# H01R0_Frontend_1.net
KiCad netlist of a schematic drawn in Altium Designer
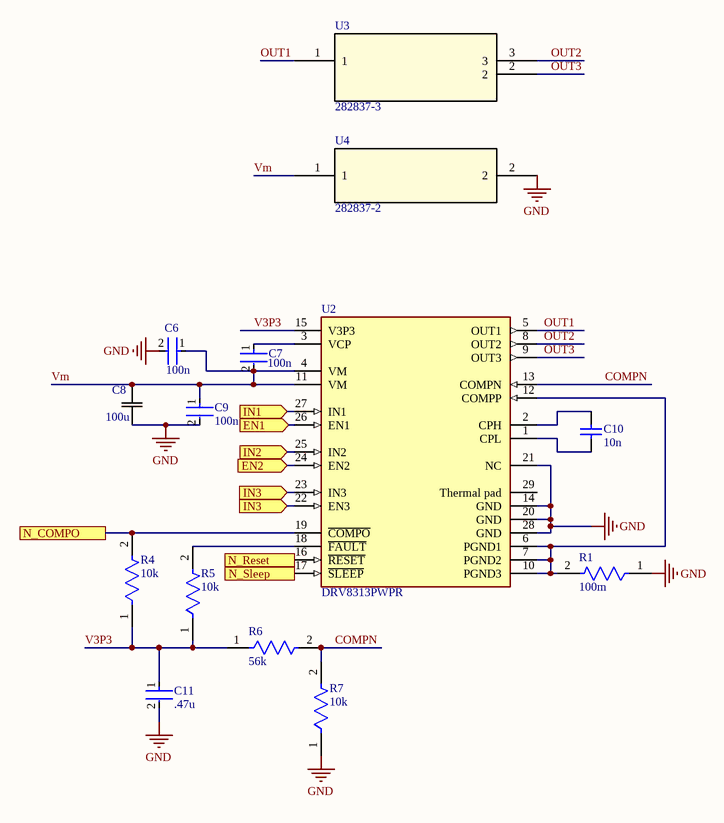
[diagram p0: H01R0_Frontend 1.SchDoc]

(export (version "E")
  (design (tool "Eeschema 10.0.6"))
  (components
    (comp (ref "C6")
      (value "100n")
      (footprint "FP-1812-L_4_5_0_3-W_3_2_0-IPC_C")
      (description "General Purpose Ceramic Capacitor, 1812, 100nF, 10%, X7R, 15%, 100V")
      (fields (field (name "TOLERANCE") "10%") (field (name "VOLTAGE") "100V"))
      (libsource (lib "Altium Content Vault") (part "02cd4be3c70576c341d710602a673aa"))
    )
    (comp (ref "C7")
      (value "100n")
      (footprint "FP-1812-L_4_5_0_3-W_3_2_0-IPC_C")
      (description "General Purpose Ceramic Capacitor, 1812, 100nF, 10%, X7R, 15%, 100V")
      (fields (field (name "TOLERANCE") "10%") (field (name "VOLTAGE") "100V"))
      (libsource (lib "Altium Content Vault") (part "02cd4be3c70576c341d710602a673aa"))
    )
    (comp (ref "C8")
      (value "100u")
      (footprint "CAP_CL31A_SAM")
      (description "No Description Available")
      (fields
        (field (name "MANUFACTURER_PART_NUMBER") "CL31A107MQHNNWE")
        (field (name "COPYRIGHT") "Copyright (C) 2025 Ultra Librarian. All rights reserved.")
      )
      (libsource (lib "Phone Jig") (part "CL31A107MQHNNWE"))
    )
    (comp (ref "C9")
      (value "100n")
      (footprint "FP-1812-L_4_5_0_3-W_3_2_0-IPC_C")
      (description "General Purpose Ceramic Capacitor, 1812, 100nF, 10%, X7R, 15%, 100V")
      (fields (field (name "TOLERANCE") "10%") (field (name "VOLTAGE") "100V"))
      (libsource (lib "Altium Content Vault") (part "02cd4be3c70576c341d710602a673aa"))
    )
    (comp (ref "C10")
      (value "10n")
      (footprint "CAPC1608X92X38NL15T08")
      (fields (field (name "PART NUMBER") "VJ0603Y103KXBAC") (field (name "MANUFACTURER") "Vitramon"))
      (libsource (lib "Altium Content Vault") (part "CAP"))
    )
    (comp (ref "C11")
      (value ".47u")
      (footprint "FP-C1206C-EB-MFG")
      (description "C1206 0.47 μF X7R 10.00% 25 V")
      (fields
        (field (name "OCTOPART") "https://octopart.com/c1206c474k3rac7210-kemet-13188669")
        (field (name "MANUFACTURER") "KEMET")
      )
      (libsource (lib "Altium Content Vault") (part "b4654b650e69147ec39a6b967a45e02"))
    )
    (comp (ref "R1")
      (value "100m")
      (footprint "FP-PCS2512-IPC_C")
      (description "2W 0.100 OHMS 0.5% 2512")
      (libsource (lib "Altium Content Vault") (part "1029c3af85768c4190bb7ad29bc67b5"))
    )
    (comp (ref "R4")
      (value "10k")
      (footprint "FP-CRCW2010-e3-IPC_B")
      (description "RES Thick Film, 10kΩ, 1%, 0.75W, 100ppm/°C, 2010")
      (fields (field (name "TOLERANCE") "1%"))
      (libsource (lib "Altium Content Vault") (part "1029c3af85768c4190bb7ad29bc67b5"))
    )
    (comp (ref "R5")
      (value "10k")
      (footprint "FP-CRCW2010-e3-IPC_B")
      (description "RES Thick Film, 10kΩ, 1%, 0.75W, 100ppm/°C, 2010")
      (fields (field (name "TOLERANCE") "1%"))
      (libsource (lib "Altium Content Vault") (part "1029c3af85768c4190bb7ad29bc67b5"))
    )
    (comp (ref "R6")
      (value "56k")
      (footprint "FP-SMA-A0207-MFG")
      (description "SMA-A 0207 56KΩ 1W 15ppm/ºC 0.10% 350V")
      (fields (field (name "MANUFACTURER") "TE Connectivity") (field (name "TOLERANCE") "0.001"))
      (libsource (lib "Altium Content Vault") (part "1029c3af85768c4190bb7ad29bc67b5"))
    )
    (comp (ref "R7")
      (value "10k")
      (footprint "FP-CRCW2010-e3-IPC_B")
      (description "RES Thick Film, 10kΩ, 1%, 0.75W, 100ppm/°C, 2010")
      (fields (field (name "TOLERANCE") "1%"))
      (libsource (lib "Altium Content Vault") (part "1029c3af85768c4190bb7ad29bc67b5"))
    )
    (comp (ref "U2")
      (value "DRV8313PWPR")
      (footprint "FP-PWP0028C-IPC_B")
      (description "IC MOTOR DRIVER 8V-60V 28HTSSOP")
      (libsource (lib "Altium Content Vault") (part "6c5e8d1d79df7918d4eb9ae5de6b4b8"))
    )
    (comp (ref "U3")
      (value "282837-3")
      (footprint "282837-3_TYC")
      (description "TERMI-BLOK PCB MOUNT 3P")
      (fields (field (name "COPYRIGHT") "Copyright (C) 2025 Ultra Librarian. All rights reserved."))
      (libsource (lib "Phone Jig") (part "282837-3"))
    )
    (comp (ref "U4")
      (value "282837-2")
      (footprint "282837-2_TYC")
      (description "TERMI-BLOK PCB MOUNT 2P")
      (fields (field (name "COPYRIGHT") "Copyright (C) 2025 Ultra Librarian. All rights reserved."))
      (libsource (lib "Phone Jig") (part "282837-2"))
    )
  )
  (nets
    (net (code "1") (name "/COMPN") (class "Default")
      (node (ref "R6") (pin "2") (pinfunction "2_2") (pintype "passive"))
      (node (ref "R7") (pin "2") (pinfunction "2_2") (pintype "passive"))
      (node (ref "U2") (pin "13") (pinfunction "COMPN_13") (pintype "input"))
    )
    (net (code "2") (name "/EN1") (class "Default")
      (node (ref "U2") (pin "26") (pinfunction "EN1_26") (pintype "input"))
    )
    (net (code "3") (name "/EN2") (class "Default")
      (node (ref "U2") (pin "24") (pinfunction "EN2_24") (pintype "input"))
    )
    (net (code "4") (name "/IN1") (class "Default")
      (node (ref "U2") (pin "27") (pinfunction "IN1_27") (pintype "input"))
    )
    (net (code "5") (name "/IN2") (class "Default")
      (node (ref "U2") (pin "25") (pinfunction "IN2_25") (pintype "input"))
    )
    (net (code "6") (name "/IN3") (class "Default")
      (node (ref "U2") (pin "22") (pinfunction "EN3_22") (pintype "input"))
      (node (ref "U2") (pin "23") (pinfunction "IN3_23") (pintype "input"))
    )
    (net (code "7") (name "/N_COMPO") (class "Default")
      (node (ref "R4") (pin "2") (pinfunction "2_2") (pintype "passive"))
      (node (ref "U2") (pin "19") (pinfunction "~{COMPO}_19") (pintype "open_collector"))
    )
    (net (code "8") (name "/N_Reset") (class "Default")
      (node (ref "U2") (pin "16") (pinfunction "~{RESET}_16") (pintype "input"))
    )
    (net (code "9") (name "/N_Sleep") (class "Default")
      (node (ref "U2") (pin "17") (pinfunction "~{SLEEP}_17") (pintype "input"))
    )
    (net (code "10") (name "/OUT1") (class "Default")
      (node (ref "U2") (pin "5") (pinfunction "OUT1_5") (pintype "output"))
      (node (ref "U3") (pin "1") (pinfunction "1_1") (pintype "passive"))
    )
    (net (code "11") (name "/OUT2") (class "Default")
      (node (ref "U2") (pin "8") (pinfunction "OUT2_8") (pintype "output"))
      (node (ref "U3") (pin "3") (pinfunction "3_3") (pintype "passive"))
    )
    (net (code "12") (name "/OUT3") (class "Default")
      (node (ref "U2") (pin "9") (pinfunction "OUT3_9") (pintype "output"))
      (node (ref "U3") (pin "2") (pinfunction "2_2") (pintype "passive"))
    )
    (net (code "13") (name "/V3P3") (class "Default")
      (node (ref "C11") (pin "1") (pinfunction "1_1") (pintype "passive"))
      (node (ref "R4") (pin "1") (pinfunction "1_1") (pintype "passive"))
      (node (ref "R5") (pin "1") (pinfunction "1_1") (pintype "passive"))
      (node (ref "R6") (pin "1") (pinfunction "1_1") (pintype "passive"))
      (node (ref "U2") (pin "15") (pinfunction "V3P3_15") (pintype "power_in"))
    )
    (net (code "14") (name "/Vm") (class "Default")
      (node (ref "C6") (pin "1") (pinfunction "1_1") (pintype "passive"))
      (node (ref "C7") (pin "2") (pinfunction "2_2") (pintype "passive"))
      (node (ref "C8") (pin "2") (pinfunction "2_2") (pintype "passive"))
      (node (ref "C9") (pin "1") (pinfunction "1_1") (pintype "passive"))
      (node (ref "U2") (pin "11") (pinfunction "VM_11") (pintype "power_in"))
      (node (ref "U2") (pin "4") (pinfunction "VM_4") (pintype "power_in"))
      (node (ref "U4") (pin "1") (pinfunction "1_1") (pintype "passive"))
    )
    (net (code "15") (name "GND") (class "Default")
      (node (ref "C11") (pin "2") (pinfunction "2_2") (pintype "passive"))
      (node (ref "C6") (pin "2") (pinfunction "2_2") (pintype "passive"))
      (node (ref "C8") (pin "1") (pinfunction "1_1") (pintype "passive"))
      (node (ref "C9") (pin "2") (pinfunction "2_2") (pintype "passive"))
      (node (ref "R1") (pin "1") (pinfunction "1_1") (pintype "passive"))
      (node (ref "R7") (pin "1") (pinfunction "1_1") (pintype "passive"))
      (node (ref "U2") (pin "14") (pinfunction "GND_14") (pintype "power_in"))
      (node (ref "U2") (pin "20") (pinfunction "GND_20") (pintype "power_in"))
      (node (ref "U2") (pin "21") (pinfunction "NC_21") (pintype "passive"))
      (node (ref "U2") (pin "28") (pinfunction "GND_28") (pintype "power_in"))
      (node (ref "U4") (pin "2") (pinfunction "2_2") (pintype "passive"))
    )
    (net (code "16") (name "Net-(U2-COMPP)") (class "Default")
      (node (ref "R1") (pin "2") (pinfunction "2_2") (pintype "passive"))
      (node (ref "U2") (pin "10") (pinfunction "PGND3_10") (pintype "power_in"))
      (node (ref "U2") (pin "12") (pinfunction "COMPP_12") (pintype "input"))
      (node (ref "U2") (pin "6") (pinfunction "PGND1_6") (pintype "power_in"))
      (node (ref "U2") (pin "7") (pinfunction "PGND2_7") (pintype "power_in"))
    )
    (net (code "17") (name "Net-(U2-CPH)") (class "Default")
      (node (ref "C10") (pin "2") (pinfunction "2_2") (pintype "passive"))
      (node (ref "U2") (pin "2") (pinfunction "CPH_2") (pintype "power_in"))
    )
    (net (code "18") (name "Net-(U2-CPL)") (class "Default")
      (node (ref "C10") (pin "1") (pinfunction "1_1") (pintype "passive"))
      (node (ref "U2") (pin "1") (pinfunction "CPL_1") (pintype "power_in"))
    )
    (net (code "19") (name "Net-(U2-VCP)") (class "Default")
      (node (ref "C7") (pin "1") (pinfunction "1_1") (pintype "passive"))
      (node (ref "U2") (pin "3") (pinfunction "VCP_3") (pintype "power_in"))
    )
    (net (code "20") (name "Net-(U2-~{FAULT})") (class "Default")
      (node (ref "R5") (pin "2") (pinfunction "2_2") (pintype "passive"))
      (node (ref "U2") (pin "18") (pinfunction "~{FAULT}_18") (pintype "open_collector"))
    )
    (net (code "21") (name "unconnected-(U2-Thermal_pad-Pad29)") (class "Default")
      (node (ref "U2") (pin "29") (pinfunction "Thermal_pad_29") (pintype "power_in"))
    )
  )
)
